# Mesures.net
KiCad netlist of a schematic drawn in Altium Designer
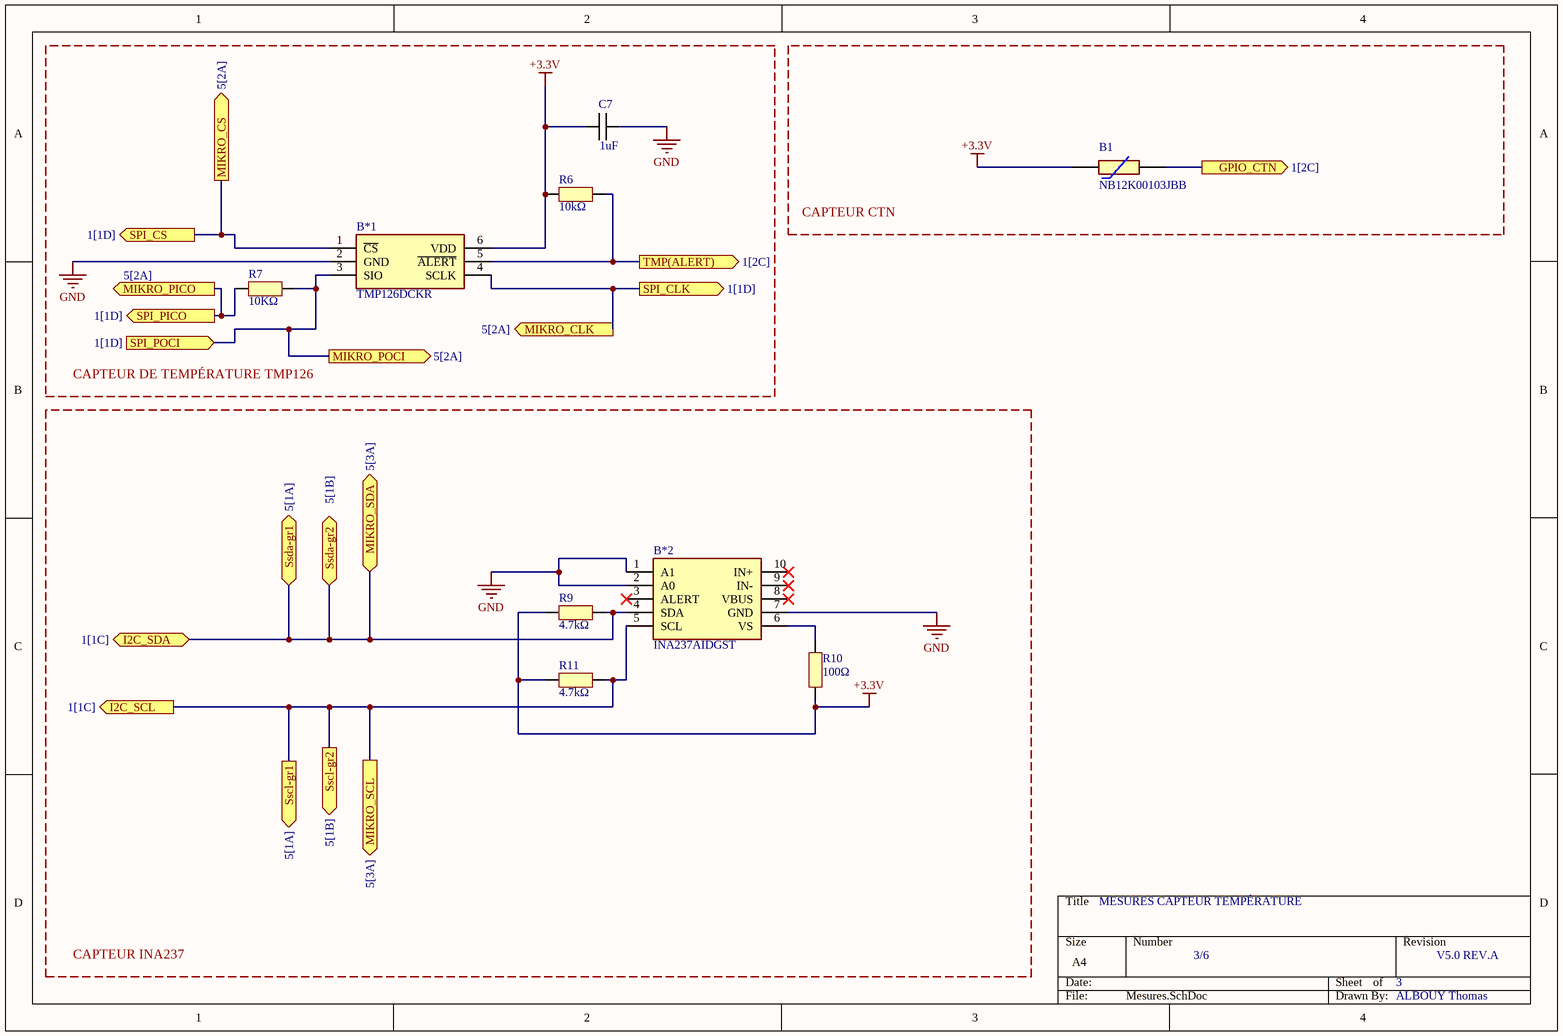
[diagram p0: Mesures.SchDoc]

(export (version "E")
  (design (tool "Eeschema 10.0.6"))
  (components
    (comp (ref "B*1")
      (value "TMP126DCKR")
      (footprint "SOT65P210X110-6N")
      (fields (field (name "MOUSER PART NUMBER") "595-TMP126DCKR"))
      (libsource (lib "SCHLibrary") (part "TMP126DCKR"))
    )
    (comp (ref "B*2")
      (value "INA237AIDGST")
      (footprint "SOP50P490X110-10N")
      (fields (field (name "MOUSER PART NUMBER") "595-INA237AIDGST"))
      (libsource (lib "SCHLibrary") (part "INA237AIDGST"))
    )
    (comp (ref "B1")
      (value "NB12K00103JBB")
      (footprint "RESC2212X50N")
      (description "NTC SMD Thermistor, NB12K, 10K, 5% AVX 10k 0805 Protection NTC Thermistor, 5s, 2 x 1.25 x 1.3mm")
      (fields (field (name "MOUSER PART NUMBER") "581-NB12K00103JBB"))
      (libsource (lib "SCHLibrary") (part "NB12K00103JBB"))
    )
    (comp (ref "C7")
      (value "1uF")
      (footprint "CAPC1005X06N")
      (libsource (lib "SCHLibrary") (part "Capacitor"))
    )
    (comp (ref "R6")
      (value "10kΩ")
      (footprint "RESC1005X06N")
      (libsource (lib "SCHLibrary") (part "Resistor"))
    )
    (comp (ref "R7")
      (value "10KΩ")
      (footprint "RESC1005X06N")
      (libsource (lib "SCHLibrary") (part "Resistor"))
    )
    (comp (ref "R9")
      (value "4.7kΩ")
      (footprint "RESC1005X06N")
      (libsource (lib "SCHLibrary") (part "Resistor"))
    )
    (comp (ref "R10") (value "100Ω") (footprint "RESC1005X06N") (libsource (lib "") (part "Resistor_1")))
    (comp (ref "R11")
      (value "4.7kΩ")
      (footprint "RESC1005X06N")
      (libsource (lib "SCHLibrary") (part "Resistor"))
    )
  )
  (nets
    (net (code "1") (name "+3.3V") (class "Default")
      (node (ref "B*1") (pin "6") (pinfunction "VDD_6") (pintype "passive"))
      (node (ref "B1") (pin "1") (pinfunction "1_1") (pintype "passive"))
      (node (ref "C7") (pin "1") (pinfunction "1_1") (pintype "passive"))
      (node (ref "R10") (pin "1") (pinfunction "1_1") (pintype "passive"))
      (node (ref "R11") (pin "1") (pinfunction "1_1") (pintype "passive"))
      (node (ref "R6") (pin "1") (pinfunction "1_1") (pintype "passive"))
      (node (ref "R9") (pin "1") (pinfunction "1_1") (pintype "passive"))
    )
    (net (code "2") (name "/GPIO_CTN") (class "Default")
      (node (ref "B1") (pin "2") (pinfunction "2_2") (pintype "passive"))
    )
    (net (code "3") (name "/I2C_SCL") (class "Default")
      (node (ref "B*2") (pin "5") (pinfunction "SCL_5") (pintype "passive"))
      (node (ref "R11") (pin "2") (pinfunction "2_2") (pintype "passive"))
    )
    (net (code "4") (name "/I2C_SDA") (class "Default")
      (node (ref "B*2") (pin "4") (pinfunction "SDA_4") (pintype "passive"))
      (node (ref "R9") (pin "2") (pinfunction "2_2") (pintype "passive"))
    )
    (net (code "5") (name "/MIKRO_CLK") (class "Default")
      (node (ref "B*1") (pin "4") (pinfunction "SCLK_4") (pintype "passive"))
    )
    (net (code "6") (name "/MIKRO_CS") (class "Default")
      (node (ref "B*1") (pin "1") (pinfunction "~{CS}_1") (pintype "passive"))
    )
    (net (code "7") (name "/MIKRO_PICO") (class "Default")
      (node (ref "R7") (pin "1") (pinfunction "1_1") (pintype "passive"))
    )
    (net (code "8") (name "/MIKRO_POCI") (class "Default")
      (node (ref "B*1") (pin "3") (pinfunction "SIO_3") (pintype "passive"))
      (node (ref "R7") (pin "2") (pinfunction "2_2") (pintype "passive"))
    )
    (net (code "9") (name "/TMP(ALERT)") (class "Default")
      (node (ref "B*1") (pin "5") (pinfunction "~{ALERT}_5") (pintype "passive"))
      (node (ref "R6") (pin "2") (pinfunction "2_2") (pintype "passive"))
    )
    (net (code "10") (name "GND") (class "Default")
      (node (ref "B*1") (pin "2") (pinfunction "GND_2") (pintype "passive"))
      (node (ref "B*2") (pin "1") (pinfunction "A1_1") (pintype "passive"))
      (node (ref "B*2") (pin "2") (pinfunction "A0_2") (pintype "passive"))
      (node (ref "B*2") (pin "7") (pinfunction "GND_7") (pintype "passive"))
      (node (ref "C7") (pin "2") (pinfunction "2_2") (pintype "passive"))
    )
    (net (code "11") (name "Net-(B*2-VS)") (class "Default")
      (node (ref "B*2") (pin "6") (pinfunction "VS_6") (pintype "passive"))
      (node (ref "R10") (pin "2") (pinfunction "2_2") (pintype "passive"))
    )
    (net (code "12") (name "unconnected-(B*2-ALERT-Pad3)") (class "Default")
      (node (ref "B*2") (pin "3") (pinfunction "ALERT_3") (pintype "passive+no_connect"))
    )
    (net (code "13") (name "unconnected-(B*2-IN+-Pad10)") (class "Default")
      (node (ref "B*2") (pin "10") (pinfunction "IN+_10") (pintype "passive+no_connect"))
    )
    (net (code "14") (name "unconnected-(B*2-IN--Pad9)") (class "Default")
      (node (ref "B*2") (pin "9") (pinfunction "IN-_9") (pintype "passive+no_connect"))
    )
    (net (code "15") (name "unconnected-(B*2-VBUS-Pad8)") (class "Default")
      (node (ref "B*2") (pin "8") (pinfunction "VBUS_8") (pintype "passive+no_connect"))
    )
  )
)
